# design.net
KiCad netlist of a schematic drawn in EasyEDA Pro
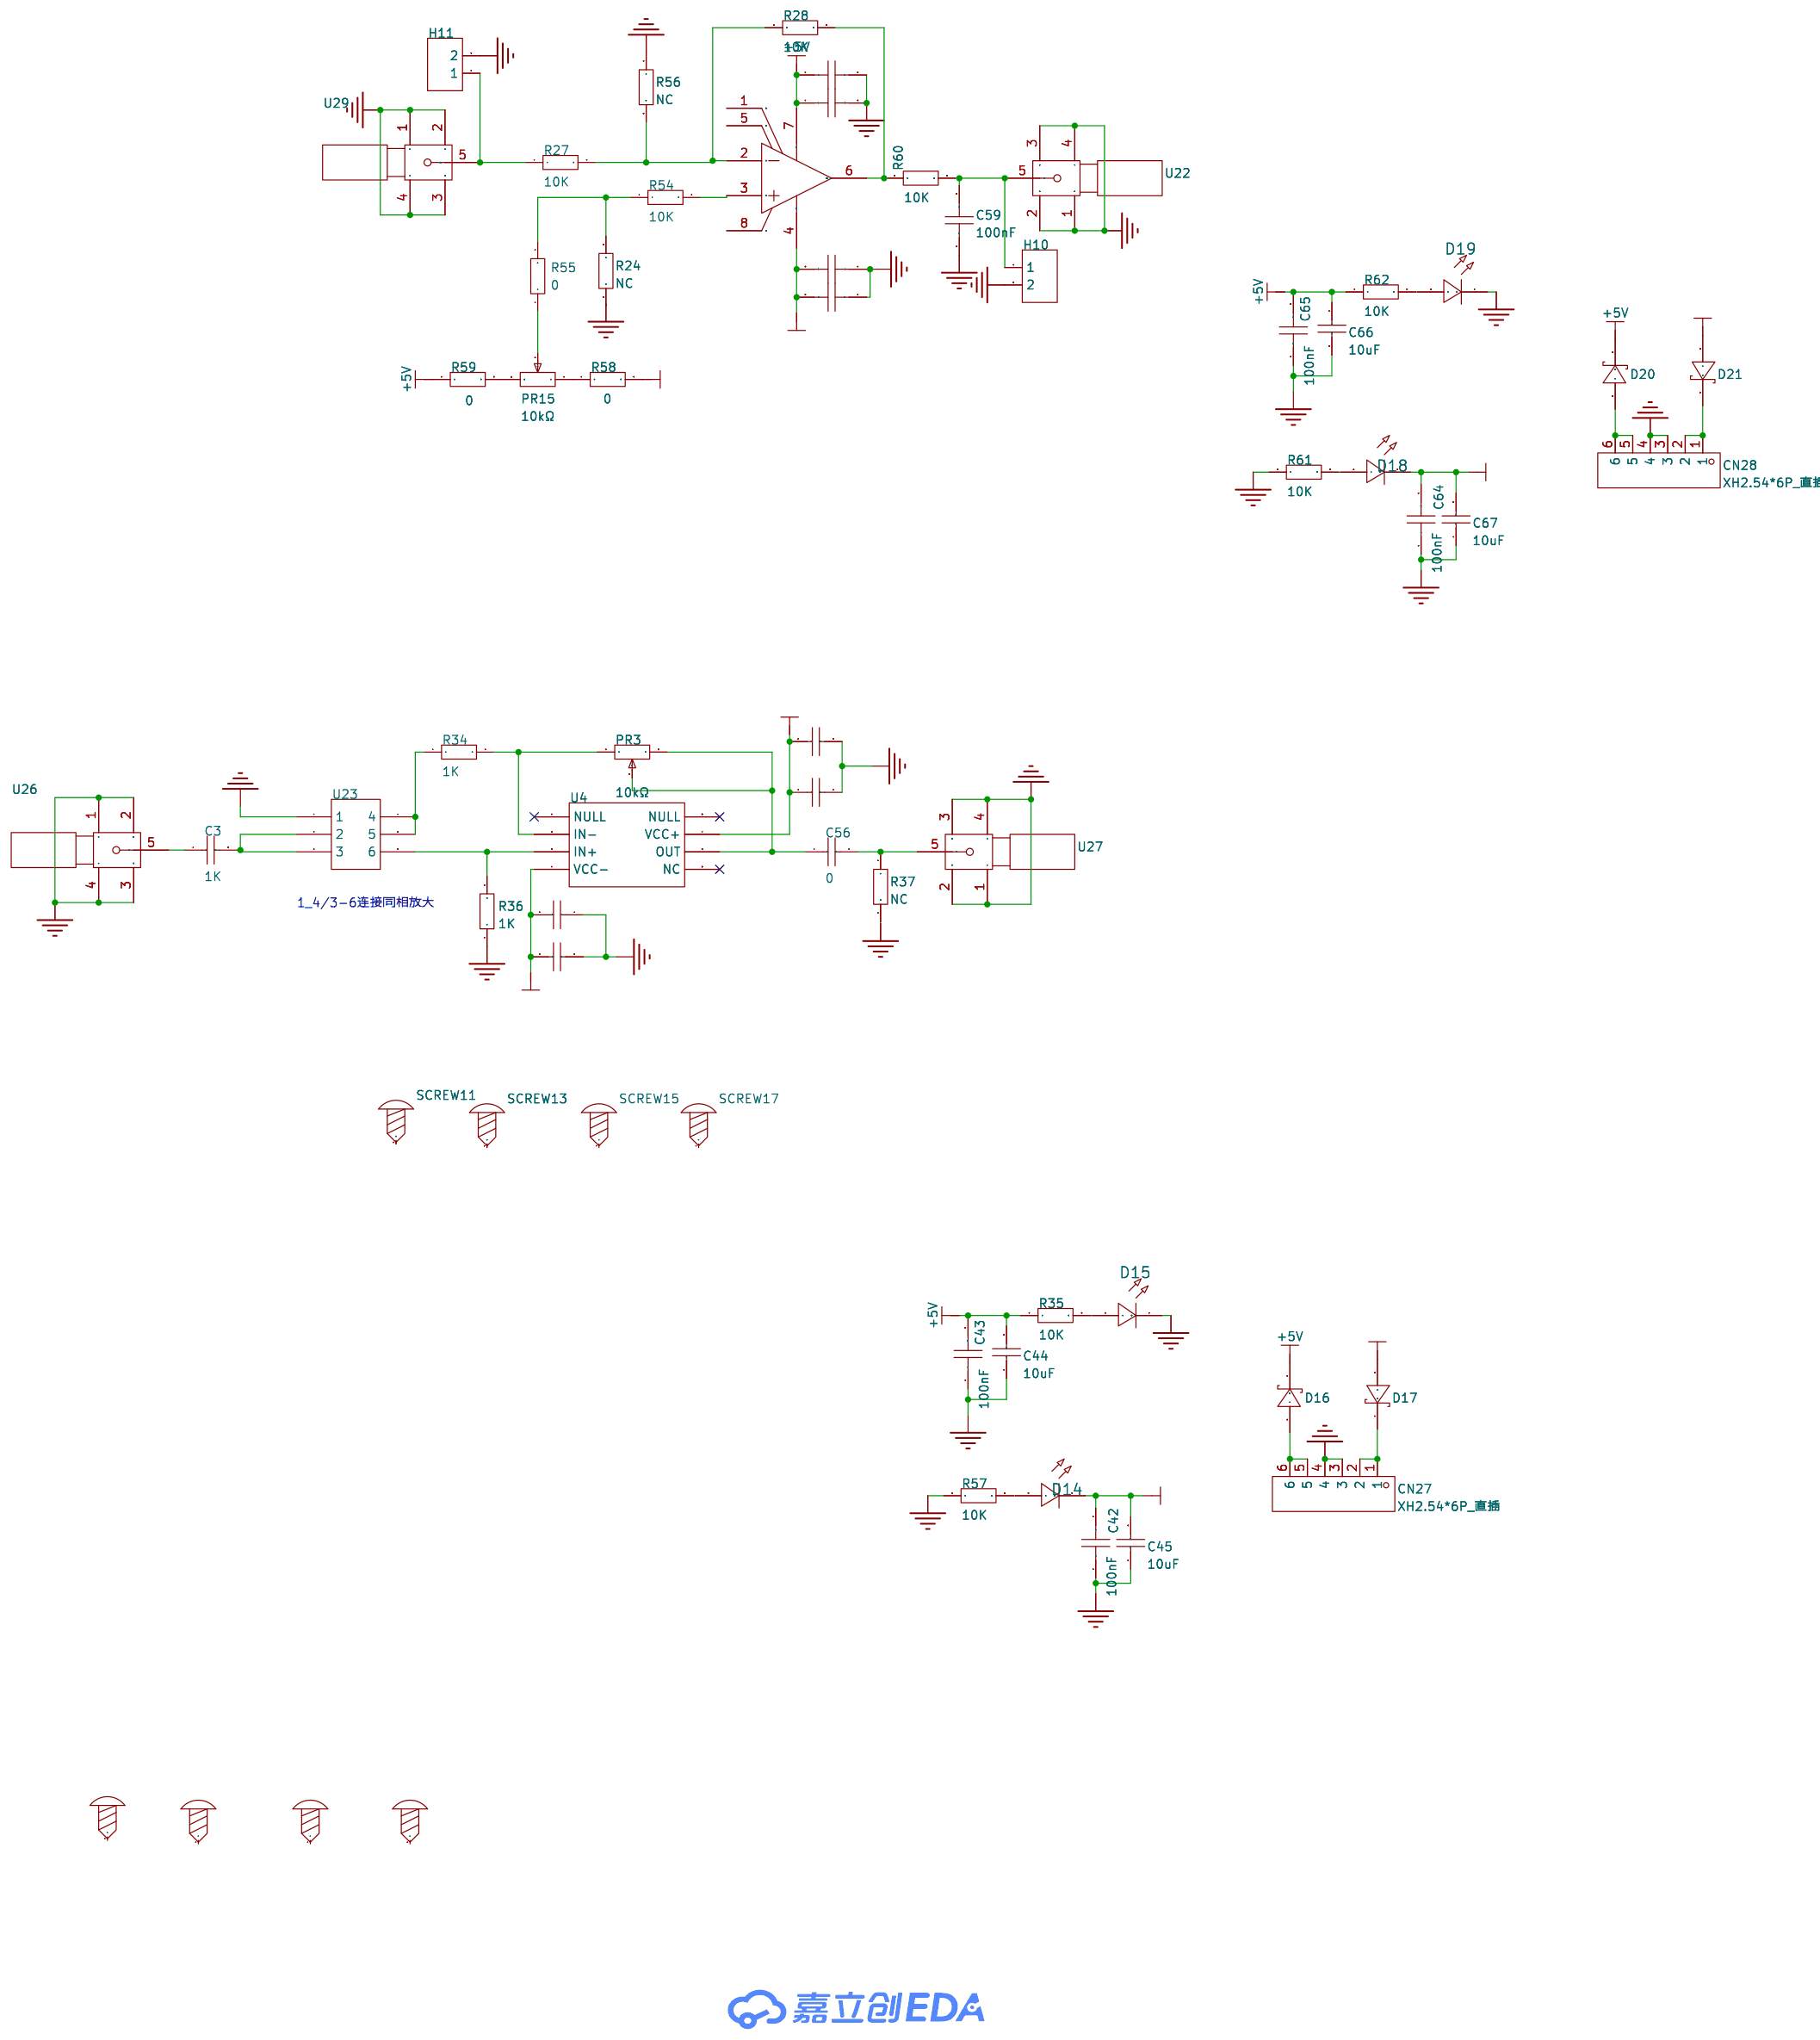
[diagram p0: schematic sheet]

(export (version "E")
  (design (tool "Eeschema 10.0.6"))
  (components
    (comp (ref "C3")
      (value "1K")
      (footprint "easyedapro:C0805")
      (description "容值:100pF;精度:±5%;额定电压:50V;材质(温度系数):C0G;")
      (fields
        (field (name "Manufacturer Part") "CL21C101JBANNNC")
        (field (name "Manufacturer") "SAMSUNG(三星)")
      )
      (libsource (lib "easyedapro") (part "CL21C101JBANNNC"))
    )
    (comp (ref "C42")
      (value "100nF")
      (footprint "easyedapro:R0805")
      (libsource (lib "easyedapro") (part "CapAcitance"))
    )
    (comp (ref "C43")
      (value "100nF")
      (footprint "easyedapro:R0805")
      (libsource (lib "easyedapro") (part "CapAcitance"))
    )
    (comp (ref "C44")
      (value "10uF")
      (footprint "easyedapro:C1210")
      (description "容值:10uF;精度:±10%;额定电压:25V;材质(温度系数):X7R;")
      (fields
        (field (name "Manufacturer Part") "CL32B106KAJNNNE")
        (field (name "Manufacturer") "SAMSUNG(三星)")
      )
      (libsource (lib "easyedapro") (part "CL32B106KAJNNNE"))
    )
    (comp (ref "C45")
      (value "10uF")
      (footprint "easyedapro:C1210")
      (description "容值:10uF;精度:±10%;额定电压:25V;材质(温度系数):X7R;")
      (fields
        (field (name "Manufacturer Part") "CL32B106KAJNNNE")
        (field (name "Manufacturer") "SAMSUNG(三星)")
      )
      (libsource (lib "easyedapro") (part "CL32B106KAJNNNE"))
    )
    (comp (ref "C54")
      (value "104")
      (footprint "easyedapro:C0805")
      (description "容值:100pF;精度:±5%;额定电压:50V;材质(温度系数):C0G;")
      (fields
        (field (name "Manufacturer Part") "CL21C101JBANNNC")
        (field (name "Manufacturer") "SAMSUNG(三星)")
      )
      (libsource (lib "easyedapro") (part "CL21C101JBANNNC"))
    )
    (comp (ref "C55")
      (value "104")
      (footprint "easyedapro:C0805")
      (description "容值:100pF;精度:±5%;额定电压:50V;材质(温度系数):C0G;")
      (fields
        (field (name "Manufacturer Part") "CL21C101JBANNNC")
        (field (name "Manufacturer") "SAMSUNG(三星)")
      )
      (libsource (lib "easyedapro") (part "CL21C101JBANNNC"))
    )
    (comp (ref "C56")
      (value "0")
      (footprint "easyedapro:C0805")
      (description "容值:100pF;精度:±5%;额定电压:50V;材质(温度系数):C0G;")
      (fields
        (field (name "Manufacturer Part") "CL21C101JBANNNC")
        (field (name "Manufacturer") "SAMSUNG(三星)")
      )
      (libsource (lib "easyedapro") (part "CL21C101JBANNNC"))
    )
    (comp (ref "C57")
      (value "104")
      (footprint "easyedapro:C0805")
      (description "容值:100pF;精度:±5%;额定电压:50V;材质(温度系数):C0G;")
      (fields
        (field (name "Manufacturer Part") "CL21C101JBANNNC")
        (field (name "Manufacturer") "SAMSUNG(三星)")
      )
      (libsource (lib "easyedapro") (part "CL21C101JBANNNC"))
    )
    (comp (ref "C58")
      (value "104")
      (footprint "easyedapro:C0805")
      (description "容值:100pF;精度:±5%;额定电压:50V;材质(温度系数):C0G;")
      (fields
        (field (name "Manufacturer Part") "CL21C101JBANNNC")
        (field (name "Manufacturer") "SAMSUNG(三星)")
      )
      (libsource (lib "easyedapro") (part "CL21C101JBANNNC"))
    )
    (comp (ref "C59")
      (value "100nF")
      (footprint "easyedapro:R0805")
      (libsource (lib "easyedapro") (part "CapAcitance"))
    )
    (comp (ref "C60")
      (value "100nF")
      (footprint "easyedapro:R0805")
      (libsource (lib "easyedapro") (part "CapAcitance"))
    )
    (comp (ref "C61")
      (value "100nF")
      (footprint "easyedapro:R0805")
      (libsource (lib "easyedapro") (part "CapAcitance"))
    )
    (comp (ref "C62")
      (value "100nF")
      (footprint "easyedapro:R0805")
      (libsource (lib "easyedapro") (part "CapAcitance"))
    )
    (comp (ref "C63")
      (value "100nF")
      (footprint "easyedapro:R0805")
      (libsource (lib "easyedapro") (part "CapAcitance"))
    )
    (comp (ref "C64")
      (value "100nF")
      (footprint "easyedapro:R0805")
      (libsource (lib "easyedapro") (part "CapAcitance"))
    )
    (comp (ref "C65")
      (value "100nF")
      (footprint "easyedapro:R0805")
      (libsource (lib "easyedapro") (part "CapAcitance"))
    )
    (comp (ref "C66")
      (value "10uF")
      (footprint "easyedapro:C1210")
      (description "容值:10uF;精度:±10%;额定电压:25V;材质(温度系数):X7R;")
      (fields
        (field (name "Manufacturer Part") "CL32B106KAJNNNE")
        (field (name "Manufacturer") "SAMSUNG(三星)")
      )
      (libsource (lib "easyedapro") (part "CL32B106KAJNNNE"))
    )
    (comp (ref "C67")
      (value "10uF")
      (footprint "easyedapro:C1210")
      (description "容值:10uF;精度:±10%;额定电压:25V;材质(温度系数):X7R;")
      (fields
        (field (name "Manufacturer Part") "CL32B106KAJNNNE")
        (field (name "Manufacturer") "SAMSUNG(三星)")
      )
      (libsource (lib "easyedapro") (part "CL32B106KAJNNNE"))
    )
    (comp (ref "CN27") (value "XH2.54*6P_直插") (libsource (lib "easyedapro") (part "XH2.54*6P_直插")))
    (comp (ref "CN28") (value "XH2.54*6P_直插") (libsource (lib "easyedapro") (part "XH2.54*6P_直插")))
    (comp (ref "D14")
      (value "~")
      (footprint "easyedapro:LED_0805")
      (libsource (lib "easyedapro") (part "LED_R"))
    )
    (comp (ref "D15")
      (value "~")
      (footprint "easyedapro:LED_0805")
      (libsource (lib "easyedapro") (part "LED_R"))
    )
    (comp (ref "D16")
      (value "SD103AWS")
      (footprint "easyedapro:SOD-323_L1.8-W1.3-LS2.5-RD")
      (description "正向压降(Vf):600mV@200mA;直流反向耐压(Vr):40V;整流电流:350mA;")
      (fields (field (name "Manufacturer") "Hottech(合科泰)"))
      (libsource (lib "easyedapro") (part "SD103AWS_C181207"))
    )
    (comp (ref "D17")
      (value "SD103AWS")
      (footprint "easyedapro:SOD-323_L1.8-W1.3-LS2.5-RD")
      (description "正向压降(Vf):600mV@200mA;直流反向耐压(Vr):40V;整流电流:350mA;")
      (fields (field (name "Manufacturer") "Hottech(合科泰)"))
      (libsource (lib "easyedapro") (part "SD103AWS_C181207"))
    )
    (comp (ref "D18")
      (value "~")
      (footprint "easyedapro:LED_0805")
      (libsource (lib "easyedapro") (part "LED_R"))
    )
    (comp (ref "D19")
      (value "~")
      (footprint "easyedapro:LED_0805")
      (libsource (lib "easyedapro") (part "LED_R"))
    )
    (comp (ref "D20")
      (value "SD103AWS")
      (footprint "easyedapro:SOD-323_L1.8-W1.3-LS2.5-RD")
      (description "正向压降(Vf):600mV@200mA;直流反向耐压(Vr):40V;整流电流:350mA;")
      (fields (field (name "Manufacturer") "Hottech(合科泰)"))
      (libsource (lib "easyedapro") (part "SD103AWS_C181207"))
    )
    (comp (ref "D21")
      (value "SD103AWS")
      (footprint "easyedapro:SOD-323_L1.8-W1.3-LS2.5-RD")
      (description "正向压降(Vf):600mV@200mA;直流反向耐压(Vr):40V;整流电流:350mA;")
      (fields (field (name "Manufacturer") "Hottech(合科泰)"))
      (libsource (lib "easyedapro") (part "SD103AWS_C181207"))
    )
    (comp (ref "H10")
      (value "~")
      (footprint "easyedapro:HDR-TH_2P-P2.54-V-F")
      (libsource (lib "easyedapro") (part "Header-Female-2.54_1x2"))
    )
    (comp (ref "H11")
      (value "~")
      (footprint "easyedapro:HDR-TH_2P-P2.54-V-F")
      (libsource (lib "easyedapro") (part "Header-Female-2.54_1x2"))
    )
    (comp (ref "PR3")
      (value "10kΩ")
      (footprint "easyedapro:R_3296")
      (libsource (lib "easyedapro") (part "R_3296"))
    )
    (comp (ref "PR15")
      (value "10kΩ")
      (footprint "easyedapro:R_3296")
      (libsource (lib "easyedapro") (part "R_3296"))
    )
    (comp (ref "R24") (value "NC") (footprint "easyedapro:R0805") (libsource (lib "easyedapro") (part "电阻")))
    (comp (ref "R27") (value "10K") (footprint "easyedapro:R0805") (libsource (lib "easyedapro") (part "电阻")))
    (comp (ref "R28") (value "10K") (footprint "easyedapro:R0805") (libsource (lib "easyedapro") (part "电阻")))
    (comp (ref "R34")
      (value "1K")
      (footprint "easyedapro:R0805")
      (description "电阻类型:厚膜电阻;阻值:51Ω;精度:±1%;功率:125mW;最大工作电压:150V;温度系数:±100ppm/°C;")
      (fields
        (field (name "Manufacturer Part") "0805W8F510JT5E")
        (field (name "Manufacturer") "UNI-ROYAL(厚声)")
      )
      (libsource (lib "easyedapro") (part "0805W8F510JT5E"))
    )
    (comp (ref "R35") (value "10K") (footprint "easyedapro:R0805") (libsource (lib "easyedapro") (part "电阻")))
    (comp (ref "R36")
      (value "1K")
      (footprint "easyedapro:R0805")
      (description "电阻类型:厚膜电阻;阻值:51Ω;精度:±1%;功率:125mW;最大工作电压:150V;温度系数:±100ppm/°C;")
      (fields
        (field (name "Manufacturer Part") "0805W8F510JT5E")
        (field (name "Manufacturer") "UNI-ROYAL(厚声)")
      )
      (libsource (lib "easyedapro") (part "0805W8F510JT5E"))
    )
    (comp (ref "R37")
      (value "NC")
      (footprint "easyedapro:R0805")
      (description "电阻类型:厚膜电阻;阻值:51Ω;精度:±1%;功率:125mW;最大工作电压:150V;温度系数:±100ppm/°C;")
      (fields
        (field (name "Manufacturer Part") "0805W8F510JT5E")
        (field (name "Manufacturer") "UNI-ROYAL(厚声)")
      )
      (libsource (lib "easyedapro") (part "0805W8F510JT5E"))
    )
    (comp (ref "R54") (value "10K") (footprint "easyedapro:R0805") (libsource (lib "easyedapro") (part "电阻")))
    (comp (ref "R55") (value "0") (footprint "easyedapro:R0805") (libsource (lib "easyedapro") (part "电阻")))
    (comp (ref "R56") (value "NC") (footprint "easyedapro:R0805") (libsource (lib "easyedapro") (part "电阻")))
    (comp (ref "R57") (value "10K") (footprint "easyedapro:R0805") (libsource (lib "easyedapro") (part "电阻")))
    (comp (ref "R58") (value "0") (footprint "easyedapro:R0805") (libsource (lib "easyedapro") (part "电阻")))
    (comp (ref "R59") (value "0") (footprint "easyedapro:R0805") (libsource (lib "easyedapro") (part "电阻")))
    (comp (ref "R60") (value "10K") (footprint "easyedapro:R0805") (libsource (lib "easyedapro") (part "电阻")))
    (comp (ref "R61") (value "10K") (footprint "easyedapro:R0805") (libsource (lib "easyedapro") (part "电阻")))
    (comp (ref "R62") (value "10K") (footprint "easyedapro:R0805") (libsource (lib "easyedapro") (part "电阻")))
    (comp (ref "SCREW11")
      (value "~")
      (footprint "easyedapro:M3螺丝")
      (libsource (lib "easyedapro") (part "螺丝孔"))
    )
    (comp (ref "SCREW13")
      (value "~")
      (footprint "easyedapro:M3螺丝")
      (libsource (lib "easyedapro") (part "螺丝孔"))
    )
    (comp (ref "SCREW15")
      (value "~")
      (footprint "easyedapro:M3螺丝")
      (libsource (lib "easyedapro") (part "螺丝孔"))
    )
    (comp (ref "SCREW17")
      (value "~")
      (footprint "easyedapro:M3螺丝")
      (libsource (lib "easyedapro") (part "螺丝孔"))
    )
    (comp (ref "SCREW18")
      (value "~")
      (footprint "easyedapro:M3螺丝")
      (libsource (lib "easyedapro") (part "螺丝孔"))
    )
    (comp (ref "SCREW19")
      (value "~")
      (footprint "easyedapro:M3螺丝")
      (libsource (lib "easyedapro") (part "螺丝孔"))
    )
    (comp (ref "SCREW20")
      (value "~")
      (footprint "easyedapro:M3螺丝")
      (libsource (lib "easyedapro") (part "螺丝孔"))
    )
    (comp (ref "SCREW21")
      (value "~")
      (footprint "easyedapro:M3螺丝")
      (libsource (lib "easyedapro") (part "螺丝孔"))
    )
    (comp (ref "U4")
      (value "~")
      (footprint "easyedapro:THS4001CD")
      (libsource (lib "easyedapro") (part "THS4001CD"))
    )
    (comp (ref "U22") (value "~") (footprint "easyedapro:SMA") (libsource (lib "easyedapro") (part "SMA")))
    (comp (ref "U23") (value "~") (libsource (lib "easyedapro") (part "3*3连跳线帽")))
    (comp (ref "U26") (value "~") (footprint "easyedapro:SMA") (libsource (lib "easyedapro") (part "SMA")))
    (comp (ref "U27") (value "~") (footprint "easyedapro:SMA") (libsource (lib "easyedapro") (part "SMA")))
    (comp (ref "U28")
      (value "OPA695IDR")
      (footprint "easyedapro:SOIC-8_L5.0-W4.0-P1.27-LS6.1-BL")
      (description "放大器数:单路;增益带宽积(GBP):-;压摆率(SR):4.3V/ns;输入偏置电流(Ib):20uA;")
      (fields (field (name "Manufacturer") "TI(德州仪器)"))
      (libsource (lib "easyedapro") (part "OPA695IDR"))
    )
    (comp (ref "U29") (value "~") (footprint "easyedapro:SMA") (libsource (lib "easyedapro") (part "SMA")))
  )
  (nets
    (net (code "1") (name "+5V") (class "Default")
      (node (ref "C43") (pin "2") (pinfunction "2_2") (pintype "input"))
      (node (ref "C44") (pin "2") (pinfunction "2_2") (pintype "input"))
      (node (ref "C55") (pin "2") (pinfunction "2_2") (pintype "input"))
      (node (ref "C58") (pin "2") (pinfunction "2_2") (pintype "input"))
      (node (ref "C62") (pin "1") (pinfunction "1_1") (pintype "input"))
      (node (ref "C63") (pin "1") (pinfunction "1_1") (pintype "input"))
      (node (ref "C65") (pin "2") (pinfunction "2_2") (pintype "input"))
      (node (ref "C66") (pin "2") (pinfunction "2_2") (pintype "input"))
      (node (ref "D16") (pin "1") (pinfunction "C_1") (pintype "unspecified"))
      (node (ref "D20") (pin "1") (pinfunction "C_1") (pintype "unspecified"))
      (node (ref "R35") (pin "1") (pinfunction "1_1") (pintype "input"))
      (node (ref "R59") (pin "1") (pinfunction "1_1") (pintype "input"))
      (node (ref "R62") (pin "1") (pinfunction "1_1") (pintype "input"))
      (node (ref "U28") (pin "7") (pinfunction "+VS_7") (pintype "unspecified"))
      (node (ref "U4") (pin "7") (pinfunction "VCC+_7") (pintype "input"))
    )
    (net (code "2") (name "-5V") (class "Default")
      (node (ref "C42") (pin "2") (pinfunction "2_2") (pintype "input"))
      (node (ref "C45") (pin "2") (pinfunction "2_2") (pintype "input"))
      (node (ref "C54") (pin "2") (pinfunction "2_2") (pintype "input"))
      (node (ref "C57") (pin "2") (pinfunction "2_2") (pintype "input"))
      (node (ref "C60") (pin "2") (pinfunction "2_2") (pintype "input"))
      (node (ref "C61") (pin "2") (pinfunction "2_2") (pintype "input"))
      (node (ref "C64") (pin "2") (pinfunction "2_2") (pintype "input"))
      (node (ref "C67") (pin "2") (pinfunction "2_2") (pintype "input"))
      (node (ref "D14") (pin "1") (pinfunction "C_1") (pintype "input"))
      (node (ref "D17") (pin "2") (pinfunction "A_2") (pintype "unspecified"))
      (node (ref "D18") (pin "1") (pinfunction "C_1") (pintype "input"))
      (node (ref "D21") (pin "2") (pinfunction "A_2") (pintype "unspecified"))
      (node (ref "R58") (pin "2") (pinfunction "2_2") (pintype "input"))
      (node (ref "U28") (pin "4") (pinfunction "-VS_4") (pintype "unspecified"))
      (node (ref "U4") (pin "4") (pinfunction "VCC-_4") (pintype "input"))
    )
    (net (code "3") (name "GND") (class "Default")
      (node (ref "C42") (pin "1") (pinfunction "1_1") (pintype "input"))
      (node (ref "C43") (pin "1") (pinfunction "1_1") (pintype "input"))
      (node (ref "C44") (pin "1") (pinfunction "1_1") (pintype "input"))
      (node (ref "C45") (pin "1") (pinfunction "1_1") (pintype "input"))
      (node (ref "C54") (pin "1") (pinfunction "1_1") (pintype "input"))
      (node (ref "C55") (pin "1") (pinfunction "1_1") (pintype "input"))
      (node (ref "C57") (pin "1") (pinfunction "1_1") (pintype "input"))
      (node (ref "C58") (pin "1") (pinfunction "1_1") (pintype "input"))
      (node (ref "C59") (pin "1") (pinfunction "1_1") (pintype "input"))
      (node (ref "C60") (pin "1") (pinfunction "1_1") (pintype "input"))
      (node (ref "C61") (pin "1") (pinfunction "1_1") (pintype "input"))
      (node (ref "C62") (pin "2") (pinfunction "2_2") (pintype "input"))
      (node (ref "C63") (pin "2") (pinfunction "2_2") (pintype "input"))
      (node (ref "C64") (pin "1") (pinfunction "1_1") (pintype "input"))
      (node (ref "C65") (pin "1") (pinfunction "1_1") (pintype "input"))
      (node (ref "C66") (pin "1") (pinfunction "1_1") (pintype "input"))
      (node (ref "C67") (pin "1") (pinfunction "1_1") (pintype "input"))
      (node (ref "CN27") (pin "3") (pinfunction "3_3") (pintype "unspecified"))
      (node (ref "CN27") (pin "4") (pinfunction "4_4") (pintype "unspecified"))
      (node (ref "CN28") (pin "3") (pinfunction "3_3") (pintype "unspecified"))
      (node (ref "CN28") (pin "4") (pinfunction "4_4") (pintype "unspecified"))
      (node (ref "D15") (pin "1") (pinfunction "C_1") (pintype "input"))
      (node (ref "D19") (pin "1") (pinfunction "C_1") (pintype "input"))
      (node (ref "H10") (pin "2") (pinfunction "2_2") (pintype "input"))
      (node (ref "H11") (pin "2") (pinfunction "2_2") (pintype "input"))
      (node (ref "R24") (pin "1") (pinfunction "1_1") (pintype "input"))
      (node (ref "R36") (pin "1") (pinfunction "1_1") (pintype "input"))
      (node (ref "R37") (pin "2") (pinfunction "2_2") (pintype "input"))
      (node (ref "R56") (pin "1") (pinfunction "1_1") (pintype "input"))
      (node (ref "R57") (pin "1") (pinfunction "1_1") (pintype "input"))
      (node (ref "R61") (pin "1") (pinfunction "1_1") (pintype "input"))
      (node (ref "U22") (pin "1") (pinfunction "1_1") (pintype "input"))
      (node (ref "U22") (pin "2") (pinfunction "2_2") (pintype "input"))
      (node (ref "U22") (pin "3") (pinfunction "3_3") (pintype "input"))
      (node (ref "U22") (pin "4") (pinfunction "4_4") (pintype "input"))
      (node (ref "U23") (pin "1") (pinfunction "1_1") (pintype "input"))
      (node (ref "U26") (pin "1") (pinfunction "1_1") (pintype "input"))
      (node (ref "U26") (pin "2") (pinfunction "2_2") (pintype "input"))
      (node (ref "U26") (pin "3") (pinfunction "3_3") (pintype "input"))
      (node (ref "U26") (pin "4") (pinfunction "4_4") (pintype "input"))
      (node (ref "U27") (pin "1") (pinfunction "1_1") (pintype "input"))
      (node (ref "U27") (pin "2") (pinfunction "2_2") (pintype "input"))
      (node (ref "U27") (pin "3") (pinfunction "3_3") (pintype "input"))
      (node (ref "U27") (pin "4") (pinfunction "4_4") (pintype "input"))
      (node (ref "U29") (pin "1") (pinfunction "1_1") (pintype "input"))
      (node (ref "U29") (pin "2") (pinfunction "2_2") (pintype "input"))
      (node (ref "U29") (pin "3") (pinfunction "3_3") (pintype "input"))
      (node (ref "U29") (pin "4") (pinfunction "4_4") (pintype "input"))
    )
    (net (code "4") (name "Net-(C3-Pad1)") (class "Default")
      (node (ref "C3") (pin "1") (pinfunction "1_1") (pintype "input"))
      (node (ref "U26") (pin "5") (pinfunction "5_5") (pintype "input"))
    )
    (net (code "5") (name "Net-(C3-Pad2)") (class "Default")
      (node (ref "C3") (pin "2") (pinfunction "2_2") (pintype "input"))
      (node (ref "U23") (pin "2") (pinfunction "2_2") (pintype "input"))
      (node (ref "U23") (pin "3") (pinfunction "3_3") (pintype "input"))
    )
    (net (code "6") (name "Net-(C56-Pad2)") (class "Default")
      (node (ref "C56") (pin "2") (pinfunction "2_2") (pintype "input"))
      (node (ref "R37") (pin "1") (pinfunction "1_1") (pintype "input"))
      (node (ref "U27") (pin "5") (pinfunction "5_5") (pintype "input"))
    )
    (net (code "7") (name "Net-(C59-Pad2)") (class "Default")
      (node (ref "C59") (pin "2") (pinfunction "2_2") (pintype "input"))
      (node (ref "H10") (pin "1") (pinfunction "1_1") (pintype "input"))
      (node (ref "R60") (pin "2") (pinfunction "2_2") (pintype "input"))
      (node (ref "U22") (pin "5") (pinfunction "5_5") (pintype "input"))
    )
    (net (code "8") (name "Net-(D14-A)") (class "Default")
      (node (ref "D14") (pin "2") (pinfunction "A_2") (pintype "input"))
      (node (ref "R57") (pin "2") (pinfunction "2_2") (pintype "input"))
    )
    (net (code "9") (name "Net-(D15-A)") (class "Default")
      (node (ref "D15") (pin "2") (pinfunction "A_2") (pintype "input"))
      (node (ref "R35") (pin "2") (pinfunction "2_2") (pintype "input"))
    )
    (net (code "10") (name "Net-(D16-A)") (class "Default")
      (node (ref "CN27") (pin "5") (pinfunction "5_5") (pintype "unspecified"))
      (node (ref "CN27") (pin "6") (pinfunction "6_6") (pintype "unspecified"))
      (node (ref "D16") (pin "2") (pinfunction "A_2") (pintype "unspecified"))
    )
    (net (code "11") (name "Net-(D17-C)") (class "Default")
      (node (ref "CN27") (pin "1") (pinfunction "1_1") (pintype "unspecified"))
      (node (ref "CN27") (pin "2") (pinfunction "2_2") (pintype "unspecified"))
      (node (ref "D17") (pin "1") (pinfunction "C_1") (pintype "unspecified"))
    )
    (net (code "12") (name "Net-(D18-A)") (class "Default")
      (node (ref "D18") (pin "2") (pinfunction "A_2") (pintype "input"))
      (node (ref "R61") (pin "2") (pinfunction "2_2") (pintype "input"))
    )
    (net (code "13") (name "Net-(D19-A)") (class "Default")
      (node (ref "D19") (pin "2") (pinfunction "A_2") (pintype "input"))
      (node (ref "R62") (pin "2") (pinfunction "2_2") (pintype "input"))
    )
    (net (code "14") (name "Net-(D20-A)") (class "Default")
      (node (ref "CN28") (pin "5") (pinfunction "5_5") (pintype "unspecified"))
      (node (ref "CN28") (pin "6") (pinfunction "6_6") (pintype "unspecified"))
      (node (ref "D20") (pin "2") (pinfunction "A_2") (pintype "unspecified"))
    )
    (net (code "15") (name "Net-(D21-C)") (class "Default")
      (node (ref "CN28") (pin "1") (pinfunction "1_1") (pintype "unspecified"))
      (node (ref "CN28") (pin "2") (pinfunction "2_2") (pintype "unspecified"))
      (node (ref "D21") (pin "1") (pinfunction "C_1") (pintype "unspecified"))
    )
    (net (code "16") (name "Net-(H11-Pad1)") (class "Default")
      (node (ref "H11") (pin "1") (pinfunction "1_1") (pintype "input"))
      (node (ref "R27") (pin "1") (pinfunction "1_1") (pintype "input"))
      (node (ref "U29") (pin "5") (pinfunction "5_5") (pintype "input"))
    )
    (net (code "17") (name "Net-(PR15-Pad1)") (class "Default")
      (node (ref "PR15") (pin "1") (pinfunction "1_1") (pintype "input"))
      (node (ref "R58") (pin "1") (pinfunction "1_1") (pintype "input"))
    )
    (net (code "18") (name "Net-(PR15-Pad2)") (class "Default")
      (node (ref "PR15") (pin "2") (pinfunction "2_2") (pintype "input"))
      (node (ref "R55") (pin "1") (pinfunction "1_1") (pintype "input"))
    )
    (net (code "19") (name "Net-(PR15-Pad3)") (class "Default")
      (node (ref "PR15") (pin "3") (pinfunction "3_3") (pintype "input"))
      (node (ref "R59") (pin "2") (pinfunction "2_2") (pintype "input"))
    )
    (net (code "20") (name "Net-(R24-Pad2)") (class "Default")
      (node (ref "R24") (pin "2") (pinfunction "2_2") (pintype "input"))
      (node (ref "R54") (pin "1") (pinfunction "1_1") (pintype "input"))
      (node (ref "R55") (pin "2") (pinfunction "2_2") (pintype "input"))
    )
    (net (code "21") (name "Net-(R34-Pad1)") (class "Default")
      (node (ref "R34") (pin "1") (pinfunction "1_1") (pintype "input"))
      (node (ref "U23") (pin "4") (pinfunction "4_4") (pintype "input"))
      (node (ref "U23") (pin "5") (pinfunction "5_5") (pintype "input"))
    )
    (net (code "22") (name "Net-(U4-IN+)") (class "Default")
      (node (ref "R36") (pin "2") (pinfunction "2_2") (pintype "input"))
      (node (ref "U23") (pin "6") (pinfunction "6_6") (pintype "input"))
      (node (ref "U4") (pin "3") (pinfunction "IN+_3") (pintype "input"))
    )
    (net (code "23") (name "Net-(U4-IN-)") (class "Default")
      (node (ref "PR3") (pin "1") (pinfunction "1_1") (pintype "input"))
      (node (ref "R34") (pin "2") (pinfunction "2_2") (pintype "input"))
      (node (ref "U4") (pin "2") (pinfunction "IN-_2") (pintype "input"))
    )
    (net (code "24") (name "Net-(U4-OUT)") (class "Default")
      (node (ref "C56") (pin "1") (pinfunction "1_1") (pintype "input"))
      (node (ref "PR3") (pin "2") (pinfunction "2_2") (pintype "input"))
      (node (ref "PR3") (pin "3") (pinfunction "3_3") (pintype "input"))
      (node (ref "U4") (pin "6") (pinfunction "OUT_6") (pintype "input"))
    )
    (net (code "25") (name "Net-(U28-+IN)") (class "Default")
      (node (ref "R54") (pin "2") (pinfunction "2_2") (pintype "input"))
      (node (ref "U28") (pin "3") (pinfunction "+IN_3") (pintype "unspecified"))
    )
    (net (code "26") (name "Net-(U28--IN)") (class "Default")
      (node (ref "R27") (pin "2") (pinfunction "2_2") (pintype "input"))
      (node (ref "R28") (pin "1") (pinfunction "1_1") (pintype "input"))
      (node (ref "R56") (pin "2") (pinfunction "2_2") (pintype "input"))
      (node (ref "U28") (pin "2") (pinfunction "-IN_2") (pintype "unspecified"))
    )
    (net (code "27") (name "Net-(U28-Output)") (class "Default")
      (node (ref "R28") (pin "2") (pinfunction "2_2") (pintype "input"))
      (node (ref "R60") (pin "1") (pinfunction "1_1") (pintype "input"))
      (node (ref "U28") (pin "6") (pinfunction "Output_6") (pintype "output"))
    )
    (net (code "28") (name "unconnected-(SCREW11-Pad1)") (class "Default")
      (node (ref "SCREW11") (pin "1") (pinfunction "1_1") (pintype "input"))
    )
    (net (code "29") (name "unconnected-(SCREW13-Pad1)") (class "Default")
      (node (ref "SCREW13") (pin "1") (pinfunction "1_1") (pintype "input"))
    )
    (net (code "30") (name "unconnected-(SCREW15-Pad1)") (class "Default")
      (node (ref "SCREW15") (pin "1") (pinfunction "1_1") (pintype "input"))
    )
    (net (code "31") (name "unconnected-(SCREW17-Pad1)") (class "Default")
      (node (ref "SCREW17") (pin "1") (pinfunction "1_1") (pintype "input"))
    )
    (net (code "32") (name "unconnected-(SCREW18-Pad1)") (class "Default")
      (node (ref "SCREW18") (pin "1") (pinfunction "1_1") (pintype "input"))
    )
    (net (code "33") (name "unconnected-(SCREW19-Pad1)") (class "Default")
      (node (ref "SCREW19") (pin "1") (pinfunction "1_1") (pintype "input"))
    )
    (net (code "34") (name "unconnected-(SCREW20-Pad1)") (class "Default")
      (node (ref "SCREW20") (pin "1") (pinfunction "1_1") (pintype "input"))
    )
    (net (code "35") (name "unconnected-(SCREW21-Pad1)") (class "Default")
      (node (ref "SCREW21") (pin "1") (pinfunction "1_1") (pintype "input"))
    )
    (net (code "36") (name "unconnected-(U4-NC-Pad5)") (class "Default")
      (node (ref "U4") (pin "5") (pinfunction "NC_5") (pintype "input+no_connect"))
    )
    (net (code "37") (name "unconnected-(U4-NULL-Pad1)") (class "Default")
      (node (ref "U4") (pin "1") (pinfunction "NULL_1") (pintype "input+no_connect"))
    )
    (net (code "38") (name "unconnected-(U4-NULL-Pad8)") (class "Default")
      (node (ref "U4") (pin "8") (pinfunction "NULL_8") (pintype "input+no_connect"))
    )
    (net (code "39") (name "unconnected-(U28-DIS#-Pad8)") (class "Default")
      (node (ref "U28") (pin "8") (pinfunction "DIS#_8") (pintype "unspecified"))
    )
    (net (code "40") (name "unconnected-(U28-NC-Pad1)") (class "Default")
      (node (ref "U28") (pin "1") (pinfunction "NC_1") (pintype "unspecified"))
    )
    (net (code "41") (name "unconnected-(U28-NC-Pad5)") (class "Default")
      (node (ref "U28") (pin "5") (pinfunction "NC_5") (pintype "unspecified"))
    )
  )
)
